# AD9954.net
KiCad netlist of a schematic drawn in Altium Designer
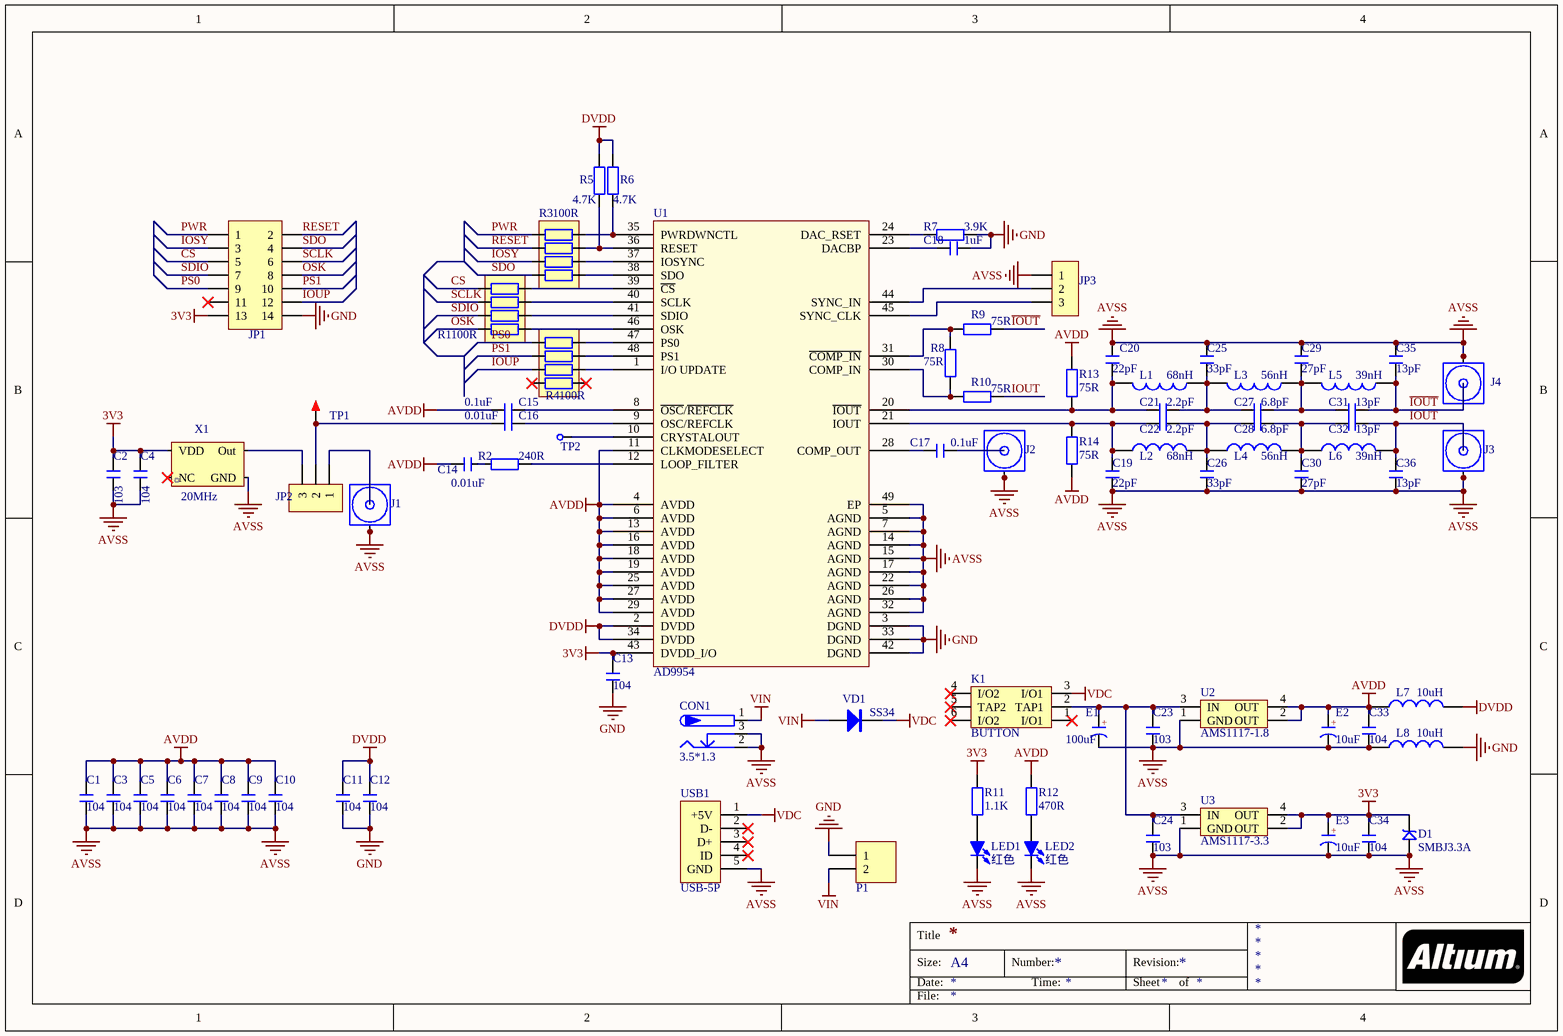
[diagram p0: AD9954模块.SchDoc]

(export (version "E")
  (design (tool "Eeschema 10.0.6"))
  (components
    (comp (ref "C1")
      (value "104")
      (footprint "C 0603")
      (description "无极性贴片电容")
      (fields (field (name "版权归属") "源创客"))
      (libsource (lib "电阻-电容-电感") (part "C"))
    )
    (comp (ref "C2")
      (value "103")
      (footprint "C 0603")
      (description "无极性贴片电容")
      (fields (field (name "版权归属") "源创客"))
      (libsource (lib "电阻-电容-电感") (part "C"))
    )
    (comp (ref "C3")
      (value "104")
      (footprint "C 0603")
      (description "无极性贴片电容")
      (fields (field (name "版权归属") "源创客"))
      (libsource (lib "电阻-电容-电感") (part "C"))
    )
    (comp (ref "C4")
      (value "104")
      (footprint "C 0603")
      (description "无极性贴片电容")
      (fields (field (name "版权归属") "源创客"))
      (libsource (lib "电阻-电容-电感") (part "C"))
    )
    (comp (ref "C5")
      (value "104")
      (footprint "C 0603")
      (description "无极性贴片电容")
      (fields (field (name "版权归属") "源创客"))
      (libsource (lib "电阻-电容-电感") (part "C"))
    )
    (comp (ref "C6")
      (value "104")
      (footprint "C 0603")
      (description "无极性贴片电容")
      (fields (field (name "版权归属") "源创客"))
      (libsource (lib "电阻-电容-电感") (part "C"))
    )
    (comp (ref "C7")
      (value "104")
      (footprint "C 0603")
      (description "无极性贴片电容")
      (fields (field (name "版权归属") "源创客"))
      (libsource (lib "电阻-电容-电感") (part "C"))
    )
    (comp (ref "C8")
      (value "104")
      (footprint "C 0603")
      (description "无极性贴片电容")
      (fields (field (name "版权归属") "源创客"))
      (libsource (lib "电阻-电容-电感") (part "C"))
    )
    (comp (ref "C9")
      (value "104")
      (footprint "C 0603")
      (description "无极性贴片电容")
      (fields (field (name "版权归属") "源创客"))
      (libsource (lib "电阻-电容-电感") (part "C"))
    )
    (comp (ref "C10")
      (value "104")
      (footprint "C 0603")
      (description "无极性贴片电容")
      (fields (field (name "版权归属") "源创客"))
      (libsource (lib "电阻-电容-电感") (part "C"))
    )
    (comp (ref "C11")
      (value "104")
      (footprint "C 0603")
      (description "无极性贴片电容")
      (fields (field (name "版权归属") "源创客"))
      (libsource (lib "电阻-电容-电感") (part "C"))
    )
    (comp (ref "C12")
      (value "104")
      (footprint "C 0603")
      (description "无极性贴片电容")
      (fields (field (name "版权归属") "源创客"))
      (libsource (lib "电阻-电容-电感") (part "C"))
    )
    (comp (ref "C13")
      (value "104")
      (footprint "C 0603")
      (description "无极性贴片电容")
      (fields (field (name "版权归属") "源创客"))
      (libsource (lib "电阻-电容-电感") (part "C"))
    )
    (comp (ref "C14")
      (value "0.01uF")
      (footprint "C 0603")
      (description "无极性贴片电容")
      (fields (field (name "版权归属") "源创客"))
      (libsource (lib "电阻-电容-电感") (part "C"))
    )
    (comp (ref "C15")
      (value "0.1uF")
      (footprint "C 0603")
      (description "无极性贴片电容")
      (fields (field (name "版权归属") "源创客"))
      (libsource (lib "电阻-电容-电感") (part "C"))
    )
    (comp (ref "C16")
      (value "0.01uF")
      (footprint "C 0603")
      (description "无极性贴片电容")
      (fields (field (name "版权归属") "源创客"))
      (libsource (lib "电阻-电容-电感") (part "C"))
    )
    (comp (ref "C17")
      (value "0.1uF")
      (footprint "C 0603")
      (description "无极性贴片电容")
      (fields (field (name "版权归属") "源创客"))
      (libsource (lib "电阻-电容-电感") (part "C"))
    )
    (comp (ref "C18")
      (value "1uF")
      (footprint "C 0603")
      (description "无极性贴片电容")
      (fields (field (name "版权归属") "源创客"))
      (libsource (lib "电阻-电容-电感") (part "C"))
    )
    (comp (ref "C19")
      (value "22pF")
      (footprint "C 0603")
      (description "无极性贴片电容")
      (fields (field (name "版权归属") "源创客"))
      (libsource (lib "电阻-电容-电感") (part "C"))
    )
    (comp (ref "C20")
      (value "22pF")
      (footprint "C 0603")
      (description "无极性贴片电容")
      (fields (field (name "版权归属") "源创客"))
      (libsource (lib "电阻-电容-电感") (part "C"))
    )
    (comp (ref "C21")
      (value "2.2pF")
      (footprint "C 0603")
      (description "无极性贴片电容")
      (fields (field (name "版权归属") "源创客"))
      (libsource (lib "电阻-电容-电感") (part "C"))
    )
    (comp (ref "C22")
      (value "2.2pF")
      (footprint "C 0603")
      (description "无极性贴片电容")
      (fields (field (name "版权归属") "源创客"))
      (libsource (lib "电阻-电容-电感") (part "C"))
    )
    (comp (ref "C23")
      (value "103")
      (footprint "C 0603")
      (description "无极性贴片电容")
      (fields (field (name "版权归属") "源创客"))
      (libsource (lib "电阻-电容-电感") (part "C"))
    )
    (comp (ref "C24")
      (value "103")
      (footprint "C 0603")
      (description "无极性贴片电容")
      (fields (field (name "版权归属") "源创客"))
      (libsource (lib "电阻-电容-电感") (part "C"))
    )
    (comp (ref "C25")
      (value "33pF")
      (footprint "C 0603")
      (description "无极性贴片电容")
      (fields (field (name "版权归属") "源创客"))
      (libsource (lib "电阻-电容-电感") (part "C"))
    )
    (comp (ref "C26")
      (value "33pF")
      (footprint "C 0603")
      (description "无极性贴片电容")
      (fields (field (name "版权归属") "源创客"))
      (libsource (lib "电阻-电容-电感") (part "C"))
    )
    (comp (ref "C27")
      (value "6.8pF")
      (footprint "C 0603")
      (description "无极性贴片电容")
      (fields (field (name "版权归属") "源创客"))
      (libsource (lib "电阻-电容-电感") (part "C"))
    )
    (comp (ref "C28")
      (value "6.8pF")
      (footprint "C 0603")
      (description "无极性贴片电容")
      (fields (field (name "版权归属") "源创客"))
      (libsource (lib "电阻-电容-电感") (part "C"))
    )
    (comp (ref "C29")
      (value "27pF")
      (footprint "C 0603")
      (description "无极性贴片电容")
      (fields (field (name "版权归属") "源创客"))
      (libsource (lib "电阻-电容-电感") (part "C"))
    )
    (comp (ref "C30")
      (value "27pF")
      (footprint "C 0603")
      (description "无极性贴片电容")
      (fields (field (name "版权归属") "源创客"))
      (libsource (lib "电阻-电容-电感") (part "C"))
    )
    (comp (ref "C31")
      (value "13pF")
      (footprint "C 0603")
      (description "无极性贴片电容")
      (fields (field (name "版权归属") "源创客"))
      (libsource (lib "电阻-电容-电感") (part "C"))
    )
    (comp (ref "C32")
      (value "13pF")
      (footprint "C 0603")
      (description "无极性贴片电容")
      (fields (field (name "版权归属") "源创客"))
      (libsource (lib "电阻-电容-电感") (part "C"))
    )
    (comp (ref "C33")
      (value "104")
      (footprint "C 0603")
      (description "无极性贴片电容")
      (fields (field (name "版权归属") "源创客"))
      (libsource (lib "电阻-电容-电感") (part "C"))
    )
    (comp (ref "C34")
      (value "104")
      (footprint "C 0603")
      (description "无极性贴片电容")
      (fields (field (name "版权归属") "源创客"))
      (libsource (lib "电阻-电容-电感") (part "C"))
    )
    (comp (ref "C35")
      (value "13pF")
      (footprint "C 0603")
      (description "无极性贴片电容")
      (fields (field (name "版权归属") "源创客"))
      (libsource (lib "电阻-电容-电感") (part "C"))
    )
    (comp (ref "C36")
      (value "13pF")
      (footprint "C 0603")
      (description "无极性贴片电容")
      (fields (field (name "版权归属") "源创客"))
      (libsource (lib "电阻-电容-电感") (part "C"))
    )
    (comp (ref "CON1")
      (value "3.5*1.3")
      (footprint "DC-005")
      (description "低压电源接口")
      (fields (field (name "版权归属") "源创客"))
      (libsource (lib "接口类") (part "P-DC"))
    )
    (comp (ref "D1")
      (value "SMBJ3.3A")
      (footprint "SMB")
      (description "TVS")
      (libsource (lib "阿波罗STM32F4&F7底板封装库") (part "SMBJ"))
    )
    (comp (ref "E1")
      (value "100uF")
      (footprint "CD B(3528)")
      (description "贴片钽电容")
      (fields (field (name "版权归属") "源创客"))
      (libsource (lib "电阻-电容-电感") (part "C-CD"))
    )
    (comp (ref "E2")
      (value "10uF")
      (footprint "CD B(3528)")
      (description "贴片钽电容")
      (fields (field (name "版权归属") "源创客"))
      (libsource (lib "电阻-电容-电感") (part "C-CD"))
    )
    (comp (ref "E3")
      (value "10uF")
      (footprint "CD B(3528)")
      (description "贴片钽电容")
      (fields (field (name "版权归属") "源创客"))
      (libsource (lib "电阻-电容-电感") (part "C-CD"))
    )
    (comp (ref "J1") (value "COAX") (footprint "MCX5.08-5") (libsource (lib "LIB") (part "COAX")))
    (comp (ref "J2") (value "COAX") (footprint "MCX5.08-5-H") (libsource (lib "LIB") (part "COAX")))
    (comp (ref "J3") (value "COAX") (footprint "MCX5.08-5-H") (libsource (lib "LIB") (part "COAX")))
    (comp (ref "J4") (value "COAX") (footprint "MCX5.08-5-H") (libsource (lib "LIB") (part "COAX")))
    (comp (ref "JP1")
      (value "Header 2X7")
      (footprint "HDR-7X2")
      (description "7*2P接插件")
      (fields (field (name "版权归属") "源创客"))
      (libsource (lib "接插件") (part "Header 7X2"))
    )
    (comp (ref "JP2")
      (value "HDR-1X3")
      (footprint "HDR-1X3")
      (description "3P接插件")
      (fields (field (name "版权归属") "源创客"))
      (libsource (lib "接插件") (part "Header 3"))
    )
    (comp (ref "JP3")
      (value "HDR-1X3")
      (footprint "HDR-1X3")
      (description "3P接插件")
      (fields (field (name "版权归属") "源创客"))
      (libsource (lib "") (part "Header 3_1"))
    )
    (comp (ref "K1")
      (value "BUTTON")
      (footprint "KFT DIP-8X8")
      (libsource (lib "阿波罗STM32F4&F7底板封装库") (part "BUTTON"))
    )
    (comp (ref "L1")
      (value "68nH")
      (footprint "L 0603")
      (description "小功率贴片电感")
      (fields (field (name "版权归属") "源创客"))
      (libsource (lib "电阻-电容-电感") (part "L"))
    )
    (comp (ref "L2")
      (value "68nH")
      (footprint "L 0603")
      (description "小功率贴片电感")
      (fields (field (name "版权归属") "源创客"))
      (libsource (lib "电阻-电容-电感") (part "L"))
    )
    (comp (ref "L3")
      (value "56nH")
      (footprint "L 0603")
      (description "小功率贴片电感")
      (fields (field (name "版权归属") "源创客"))
      (libsource (lib "电阻-电容-电感") (part "L"))
    )
    (comp (ref "L4")
      (value "56nH")
      (footprint "L 0603")
      (description "小功率贴片电感")
      (fields (field (name "版权归属") "源创客"))
      (libsource (lib "电阻-电容-电感") (part "L"))
    )
    (comp (ref "L5")
      (value "39nH")
      (footprint "L 0603")
      (description "小功率贴片电感")
      (fields (field (name "版权归属") "源创客"))
      (libsource (lib "电阻-电容-电感") (part "L"))
    )
    (comp (ref "L6")
      (value "39nH")
      (footprint "L 0603")
      (description "小功率贴片电感")
      (fields (field (name "版权归属") "源创客"))
      (libsource (lib "电阻-电容-电感") (part "L"))
    )
    (comp (ref "L7")
      (value "10uH")
      (footprint "L 0805")
      (description "小功率贴片电感")
      (fields (field (name "版权归属") "源创客"))
      (libsource (lib "电阻-电容-电感") (part "L"))
    )
    (comp (ref "L8")
      (value "10uH")
      (footprint "L 0805")
      (description "小功率贴片电感")
      (fields (field (name "版权归属") "源创客"))
      (libsource (lib "电阻-电容-电感") (part "L"))
    )
    (comp (ref "LED1")
      (value "红色")
      (footprint "LED 0805G")
      (description "贴片LED")
      (fields (field (name "版权归属") "源创客"))
      (libsource (lib "LED") (part "LED-SMD"))
    )
    (comp (ref "LED2")
      (value "红色")
      (footprint "LED 0805G")
      (description "贴片LED")
      (fields (field (name "版权归属") "源创客"))
      (libsource (lib "LED") (part "LED-SMD"))
    )
    (comp (ref "P1")
      (value "Header 2")
      (footprint "HDR2X1_B2")
      (description "接插件")
      (fields (field (name "PUBLISHER") "Altium Limited"))
      (libsource (lib "LIB") (part "Header 2"))
    )
    (comp (ref "R1")
      (value "100R")
      (footprint "RCA-8P4R-0603")
      (description "贴片网络排阻")
      (fields (field (name "版权归属") "源创客"))
      (libsource (lib "电阻-电容-电感") (part "R-8P4R"))
    )
    (comp (ref "R2")
      (value "240R")
      (footprint "R 0603")
      (description "贴片电阻")
      (fields (field (name "版权归属") "源创客"))
      (libsource (lib "电阻-电容-电感") (part "R"))
    )
    (comp (ref "R3")
      (value "100R")
      (footprint "RCA-8P4R-0603")
      (description "贴片网络排阻")
      (fields (field (name "版权归属") "源创客"))
      (libsource (lib "电阻-电容-电感") (part "R-8P4R"))
    )
    (comp (ref "R4")
      (value "100R")
      (footprint "RCA-8P4R-0603")
      (description "贴片网络排阻")
      (fields (field (name "版权归属") "源创客"))
      (libsource (lib "电阻-电容-电感") (part "R-8P4R"))
    )
    (comp (ref "R5")
      (value "4.7K")
      (footprint "R 0603")
      (description "贴片电阻")
      (fields (field (name "版权归属") "源创客"))
      (libsource (lib "电阻-电容-电感") (part "R"))
    )
    (comp (ref "R6")
      (value "4.7K")
      (footprint "R 0603")
      (description "贴片电阻")
      (fields (field (name "版权归属") "源创客"))
      (libsource (lib "电阻-电容-电感") (part "R"))
    )
    (comp (ref "R7")
      (value "3.9K")
      (footprint "R 0603")
      (description "贴片电阻")
      (fields (field (name "版权归属") "源创客"))
      (libsource (lib "电阻-电容-电感") (part "R"))
    )
    (comp (ref "R8")
      (value "75R")
      (footprint "R 0603")
      (description "贴片电阻")
      (fields (field (name "版权归属") "源创客"))
      (libsource (lib "电阻-电容-电感") (part "R"))
    )
    (comp (ref "R9")
      (value "75R")
      (footprint "R 0603")
      (description "贴片电阻")
      (fields (field (name "版权归属") "源创客"))
      (libsource (lib "电阻-电容-电感") (part "R"))
    )
    (comp (ref "R10")
      (value "75R")
      (footprint "R 0603")
      (description "贴片电阻")
      (fields (field (name "版权归属") "源创客"))
      (libsource (lib "电阻-电容-电感") (part "R"))
    )
    (comp (ref "R11")
      (value "1.1K")
      (footprint "R 0603")
      (description "贴片电阻")
      (fields (field (name "版权归属") "源创客"))
      (libsource (lib "电阻-电容-电感") (part "R"))
    )
    (comp (ref "R12")
      (value "470R")
      (footprint "R 0603")
      (description "贴片电阻")
      (fields (field (name "版权归属") "源创客"))
      (libsource (lib "电阻-电容-电感") (part "R"))
    )
    (comp (ref "R13")
      (value "75R")
      (footprint "R 0603")
      (description "贴片电阻")
      (fields (field (name "版权归属") "源创客"))
      (libsource (lib "电阻-电容-电感") (part "R"))
    )
    (comp (ref "R14")
      (value "75R")
      (footprint "R 0603")
      (description "贴片电阻")
      (fields (field (name "版权归属") "源创客"))
      (libsource (lib "电阻-电容-电感") (part "R"))
    )
    (comp (ref "TP1")
      (value "TEST TP")
      (footprint "TEST TP1.4_B")
      (description "测试环")
      (fields (field (name "版权归属") "源创客"))
      (libsource (lib "未分类器件") (part "TEST TP"))
    )
    (comp (ref "TP2")
      (value "CHECK")
      (footprint "CHECK-C")
      (description "测试点")
      (libsource (lib "LIB") (part "CHECK"))
    )
    (comp (ref "U1")
      (value "AD9954")
      (footprint "SV_48_4")
      (description "400MSPS、14位、1.8V CMOS、直接数字频率合成器")
      (fields (field (name "MANUFACTURER_PART_NUMBER") "AD9954YSVZ"))
      (libsource (lib "MyLibray") (part "AD9954YSVZ"))
    )
    (comp (ref "U2")
      (value "AMS1117-1.8")
      (footprint "SOT223_N")
      (libsource (lib "ATK-7016&7084 7寸RGB屏模块封装库") (part "AMS1117"))
    )
    (comp (ref "U3")
      (value "AMS1117-3.3")
      (footprint "SOT223_N")
      (libsource (lib "ATK-7016&7084 7寸RGB屏模块封装库") (part "AMS1117"))
    )
    (comp (ref "USB1")
      (value "USB-5P")
      (footprint "USB-MICRO_B")
      (description "微型USB母座")
      (fields (field (name "版权归属") "源创客"))
      (libsource (lib "接口类") (part "USB-5P"))
    )
    (comp (ref "VD1")
      (value "SS34")
      (footprint "DIODE-SMA")
      (description "肖特基二极管")
      (fields (field (name "版权归属") "源创客"))
      (libsource (lib "二极管-整流桥") (part "SS34"))
    )
    (comp (ref "X1")
      (value "XTAL")
      (footprint "X-CPX75")
      (description "有源晶振")
      (fields (field (name "FREQUENCY") "20MHz"))
      (libsource (lib "LIB") (part "XTAL_Oscillator"))
    )
  )
  (nets
    (net (code "1") (name "/CS") (class "Default")
      (node (ref "JP1") (pin "5") (pinfunction "5_5") (pintype "passive"))
      (node (ref "R1") (pin "1") (pinfunction "1_1") (pintype "passive"))
    )
    (net (code "2") (name "/IOSY") (class "Default")
      (node (ref "JP1") (pin "3") (pinfunction "3_3") (pintype "passive"))
      (node (ref "R3") (pin "3") (pinfunction "3_3") (pintype "passive"))
    )
    (net (code "3") (name "/IOUP") (class "Default")
      (node (ref "JP1") (pin "12") (pinfunction "12_12") (pintype "passive"))
      (node (ref "R4") (pin "3") (pinfunction "3_3") (pintype "passive"))
    )
    (net (code "4") (name "/IOUT") (class "Default")
      (node (ref "C32") (pin "1") (pinfunction "1_1") (pintype "passive"))
      (node (ref "C36") (pin "1") (pinfunction "1_1") (pintype "passive"))
      (node (ref "J3") (pin "1") (pinfunction "Signal_1") (pintype "passive"))
      (node (ref "L6") (pin "2") (pinfunction "2_2") (pintype "passive"))
      (node (ref "R10") (pin "1") (pinfunction "1_1") (pintype "passive"))
    )
    (net (code "5") (name "/OSK") (class "Default")
      (node (ref "JP1") (pin "8") (pinfunction "8_8") (pintype "passive"))
      (node (ref "R1") (pin "4") (pinfunction "4_4") (pintype "passive"))
    )
    (net (code "6") (name "/PS0") (class "Default")
      (node (ref "JP1") (pin "9") (pinfunction "9_9") (pintype "passive"))
      (node (ref "R4") (pin "1") (pinfunction "1_1") (pintype "passive"))
    )
    (net (code "7") (name "/PS1") (class "Default")
      (node (ref "JP1") (pin "10") (pinfunction "10_10") (pintype "passive"))
      (node (ref "R4") (pin "2") (pinfunction "2_2") (pintype "passive"))
    )
    (net (code "8") (name "/PWR") (class "Default")
      (node (ref "JP1") (pin "1") (pinfunction "1_1") (pintype "passive"))
      (node (ref "R3") (pin "1") (pinfunction "1_1") (pintype "passive"))
    )
    (net (code "9") (name "/RESET") (class "Default")
      (node (ref "JP1") (pin "2") (pinfunction "2_2") (pintype "passive"))
      (node (ref "R3") (pin "2") (pinfunction "2_2") (pintype "passive"))
    )
    (net (code "10") (name "/SCLK") (class "Default")
      (node (ref "JP1") (pin "6") (pinfunction "6_6") (pintype "passive"))
      (node (ref "R1") (pin "2") (pinfunction "2_2") (pintype "passive"))
    )
    (net (code "11") (name "/SDIO") (class "Default")
      (node (ref "JP1") (pin "7") (pinfunction "7_7") (pintype "passive"))
      (node (ref "R1") (pin "3") (pinfunction "3_3") (pintype "passive"))
    )
    (net (code "12") (name "/SDO") (class "Default")
      (node (ref "JP1") (pin "4") (pinfunction "4_4") (pintype "passive"))
      (node (ref "R3") (pin "4") (pinfunction "4_4") (pintype "passive"))
    )
    (net (code "13") (name "/~{IOUT}") (class "Default")
      (node (ref "C31") (pin "2") (pinfunction "2_2") (pintype "passive"))
      (node (ref "C35") (pin "1") (pinfunction "1_1") (pintype "passive"))
      (node (ref "J4") (pin "1") (pinfunction "Signal_1") (pintype "passive"))
      (node (ref "L5") (pin "1") (pinfunction "1_1") (pintype "passive"))
      (node (ref "R9") (pin "1") (pinfunction "1_1") (pintype "passive"))
    )
    (net (code "14") (name "3V3") (class "Default")
      (node (ref "C13") (pin "2") (pinfunction "2_2") (pintype "passive"))
      (node (ref "C2") (pin "2") (pinfunction "2_2") (pintype "passive"))
      (node (ref "C34") (pin "2") (pinfunction "2_2") (pintype "passive"))
      (node (ref "C4") (pin "2") (pinfunction "2_2") (pintype "passive"))
      (node (ref "D1") (pin "2") (pintype "passive"))
      (node (ref "E3") (pin "1") (pinfunction "A_1") (pintype "passive"))
      (node (ref "JP1") (pin "13") (pinfunction "13_13") (pintype "passive"))
      (node (ref "R11") (pin "2") (pinfunction "2_2") (pintype "passive"))
      (node (ref "U1") (pin "43") (pinfunction "DVDD_I/O_43") (pintype "power_in"))
      (node (ref "U3") (pin "2") (pinfunction "OUT_2") (pintype "passive"))
      (node (ref "U3") (pin "4") (pinfunction "OUT_4") (pintype "passive"))
      (node (ref "X1") (pin "4") (pinfunction "VDD_4") (pintype "passive"))
    )
    (net (code "15") (name "AVDD") (class "Default")
      (node (ref "C1") (pin "2") (pinfunction "2_2") (pintype "passive"))
      (node (ref "C10") (pin "2") (pinfunction "2_2") (pintype "passive"))
      (node (ref "C14") (pin "1") (pinfunction "1_1") (pintype "passive"))
      (node (ref "C15") (pin "1") (pinfunction "1_1") (pintype "passive"))
      (node (ref "C3") (pin "2") (pinfunction "2_2") (pintype "passive"))
      (node (ref "C33") (pin "2") (pinfunction "2_2") (pintype "passive"))
      (node (ref "C5") (pin "2") (pinfunction "2_2") (pintype "passive"))
      (node (ref "C6") (pin "2") (pinfunction "2_2") (pintype "passive"))
      (node (ref "C7") (pin "2") (pinfunction "2_2") (pintype "passive"))
      (node (ref "C8") (pin "2") (pinfunction "2_2") (pintype "passive"))
      (node (ref "C9") (pin "2") (pinfunction "2_2") (pintype "passive"))
      (node (ref "E2") (pin "1") (pinfunction "A_1") (pintype "passive"))
      (node (ref "L7") (pin "1") (pinfunction "1_1") (pintype "passive"))
      (node (ref "R12") (pin "2") (pinfunction "2_2") (pintype "passive"))
      (node (ref "R13") (pin "2") (pinfunction "2_2") (pintype "passive"))
      (node (ref "R14") (pin "1") (pinfunction "1_1") (pintype "passive"))
      (node (ref "U1") (pin "11") (pinfunction "CLKMODESELECT_11") (pintype "passive"))
      (node (ref "U1") (pin "13") (pinfunction "AVDD_13") (pintype "power_in"))
      (node (ref "U1") (pin "16") (pinfunction "AVDD_16") (pintype "power_in"))
      (node (ref "U1") (pin "18") (pinfunction "AVDD_18") (pintype "power_in"))
      (node (ref "U1") (pin "19") (pinfunction "AVDD_19") (pintype "power_in"))
      (node (ref "U1") (pin "25") (pinfunction "AVDD_25") (pintype "power_in"))
      (node (ref "U1") (pin "27") (pinfunction "AVDD_27") (pintype "power_in"))
      (node (ref "U1") (pin "29") (pinfunction "AVDD_29") (pintype "power_in"))
      (node (ref "U1") (pin "4") (pinfunction "AVDD_4") (pintype "power_in"))
      (node (ref "U1") (pin "6") (pinfunction "AVDD_6") (pintype "power_in"))
      (node (ref "U2") (pin "2") (pinfunction "OUT_2") (pintype "passive"))
      (node (ref "U2") (pin "4") (pinfunction "OUT_4") (pintype "passive"))
    )
    (net (code "16") (name "AVSS") (class "Default")
      (node (ref "C1") (pin "1") (pinfunction "1_1") (pintype "passive"))
      (node (ref "C10") (pin "1") (pinfunction "1_1") (pintype "passive"))
      (node (ref "C19") (pin "2") (pinfunction "2_2") (pintype "passive"))
      (node (ref "C2") (pin "1") (pinfunction "1_1") (pintype "passive"))
      (node (ref "C20") (pin "2") (pinfunction "2_2") (pintype "passive"))
      (node (ref "C23") (pin "1") (pinfunction "1_1") (pintype "passive"))
      (node (ref "C24") (pin "1") (pinfunction "1_1") (pintype "passive"))
      (node (ref "C25") (pin "2") (pinfunction "2_2") (pintype "passive"))
      (node (ref "C26") (pin "2") (pinfunction "2_2") (pintype "passive"))
      (node (ref "C29") (pin "2") (pinfunction "2_2") (pintype "passive"))
      (node (ref "C3") (pin "1") (pinfunction "1_1") (pintype "passive"))
      (node (ref "C30") (pin "2") (pinfunction "2_2") (pintype "passive"))
      (node (ref "C33") (pin "1") (pinfunction "1_1") (pintype "passive"))
      (node (ref "C34") (pin "1") (pinfunction "1_1") (pintype "passive"))
      (node (ref "C35") (pin "2") (pinfunction "2_2") (pintype "passive"))
      (node (ref "C36") (pin "2") (pinfunction "2_2") (pintype "passive"))
      (node (ref "C4") (pin "1") (pinfunction "1_1") (pintype "passive"))
      (node (ref "C5") (pin "1") (pinfunction "1_1") (pintype "passive"))
      (node (ref "C6") (pin "1") (pinfunction "1_1") (pintype "passive"))
      (node (ref "C7") (pin "1") (pinfunction "1_1") (pintype "passive"))
      (node (ref "C8") (pin "1") (pinfunction "1_1") (pintype "passive"))
      (node (ref "C9") (pin "1") (pinfunction "1_1") (pintype "passive"))
      (node (ref "CON1") (pin "2") (pintype "power_in"))
      (node (ref "CON1") (pin "3") (pintype "power_in"))
      (node (ref "D1") (pin "1") (pintype "passive"))
      (node (ref "E1") (pin "2") (pinfunction "K_2") (pintype "passive"))
      (node (ref "E2") (pin "2") (pinfunction "K_2") (pintype "passive"))
      (node (ref "E3") (pin "2") (pinfunction "K_2") (pintype "passive"))
      (node (ref "J1") (pin "2") (pinfunction "GND_2") (pintype "passive"))
      (node (ref "J1") (pin "3") (pinfunction "GND_3") (pintype "passive"))
      (node (ref "J1") (pin "4") (pinfunction "GND_4") (pintype "passive"))
      (node (ref "J1") (pin "5") (pinfunction "GND_5") (pintype "passive"))
      (node (ref "J2") (pin "2") (pinfunction "GND_2") (pintype "passive"))
      (node (ref "J2") (pin "3") (pinfunction "GND_3") (pintype "passive"))
      (node (ref "J2") (pin "4") (pinfunction "GND_4") (pintype "passive"))
      (node (ref "J2") (pin "5") (pinfunction "GND_5") (pintype "passive"))
      (node (ref "J3") (pin "2") (pinfunction "GND_2") (pintype "passive"))
      (node (ref "J3") (pin "3") (pinfunction "GND_3") (pintype "passive"))
      (node (ref "J3") (pin "4") (pinfunction "GND_4") (pintype "passive"))
      (node (ref "J3") (pin "5") (pinfunction "GND_5") (pintype "passive"))
      (node (ref "J4") (pin "2") (pinfunction "GND_2") (pintype "passive"))
      (node (ref "J4") (pin "3") (pinfunction "GND_3") (pintype "passive"))
      (node (ref "J4") (pin "4") (pinfunction "GND_4") (pintype "passive"))
      (node (ref "J4") (pin "5") (pinfunction "GND_5") (pintype "passive"))
      (node (ref "JP3") (pin "1") (pinfunction "1_1") (pintype "passive"))
      (node (ref "L8") (pin "1") (pinfunction "1_1") (pintype "passive"))
      (node (ref "LED1") (pin "2") (pinfunction "K_2") (pintype "passive"))
      (node (ref "LED2") (pin "2") (pinfunction "K_2") (pintype "passive"))
      (node (ref "U1") (pin "14") (pinfunction "AGND_14") (pintype "passive"))
      (node (ref "U1") (pin "15") (pinfunction "AGND_15") (pintype "passive"))
      (node (ref "U1") (pin "17") (pinfunction "AGND_17") (pintype "passive"))
      (node (ref "U1") (pin "22") (pinfunction "AGND_22") (pintype "passive"))
      (node (ref "U1") (pin "26") (pinfunction "AGND_26") (pintype "passive"))
      (node (ref "U1") (pin "32") (pinfunction "AGND_32") (pintype "passive"))
      (node (ref "U1") (pin "49") (pinfunction "EP_49") (pintype "passive"))
      (node (ref "U1") (pin "5") (pinfunction "AGND_5") (pintype "passive"))
      (node (ref "U1") (pin "7") (pinfunction "AGND_7") (pintype "passive"))
      (node (ref "U2") (pin "1") (pinfunction "GND_1") (pintype "passive"))
      (node (ref "U3") (pin "1") (pinfunction "GND_1") (pintype "passive"))
      (node (ref "USB1") (pin "5") (pinfunction "GND_5") (pintype "passive"))
      (node (ref "X1") (pin "2") (pinfunction "GND_2") (pintype "passive"))
    )
    (net (code "17") (name "DVDD") (class "Default")
      (node (ref "C11") (pin "2") (pinfunction "2_2") (pintype "passive"))
      (node (ref "C12") (pin "2") (pinfunction "2_2") (pintype "passive"))
      (node (ref "L7") (pin "2") (pinfunction "2_2") (pintype "passive"))
      (node (ref "R5") (pin "2") (pinfunction "2_2") (pintype "passive"))
      (node (ref "R6") (pin "2") (pinfunction "2_2") (pintype "passive"))
      (node (ref "U1") (pin "2") (pinfunction "DVDD_2") (pintype "power_in"))
      (node (ref "U1") (pin "34") (pinfunction "DVDD_34") (pintype "power_in"))
    )
    (net (code "18") (name "GND") (class "Default")
      (node (ref "C11") (pin "1") (pinfunction "1_1") (pintype "passive"))
      (node (ref "C12") (pin "1") (pinfunction "1_1") (pintype "passive"))
      (node (ref "C13") (pin "1") (pinfunction "1_1") (pintype "passive"))
      (node (ref "C18") (pin "2") (pinfunction "2_2") (pintype "passive"))
      (node (ref "JP1") (pin "14") (pinfunction "14_14") (pintype "passive"))
      (node (ref "L8") (pin "2") (pinfunction "2_2") (pintype "passive"))
      (node (ref "P1") (pin "1") (pinfunction "1_1") (pintype "passive"))
      (node (ref "R7") (pin "2") (pinfunction "2_2") (pintype "passive"))
      (node (ref "U1") (pin "3") (pinfunction "DGND_3") (pintype "passive"))
      (node (ref "U1") (pin "33") (pinfunction "DGND_33") (pintype "passive"))
      (node (ref "U1") (pin "42") (pinfunction "DGND_42") (pintype "passive"))
    )
    (net (code "19") (name "Net-(C14-Pad2)") (class "Default")
      (node (ref "C14") (pin "2") (pinfunction "2_2") (pintype "passive"))
      (node (ref "R2") (pin "1") (pinfunction "1_1") (pintype "passive"))
    )
    (net (code "20") (name "Net-(C16-Pad1)") (class "Default")
      (node (ref "C16") (pin "1") (pinfunction "1_1") (pintype "passive"))
      (node (ref "JP2") (pin "2") (pinfunction "2_2") (pintype "passive"))
      (node (ref "TP1") (pin "1") (pinfunction "1_1") (pintype "passive"))
    )
    (net (code "21") (name "Net-(C21-Pad2)") (class "Default")
      (node (ref "C21") (pin "2") (pinfunction "2_2") (pintype "passive"))
      (node (ref "C25") (pin "1") (pinfunction "1_1") (pintype "passive"))
      (node (ref "C27") (pin "1") (pinfunction "1_1") (pintype "passive"))
      (node (ref "L1") (pin "1") (pinfunction "1_1") (pintype "passive"))
      (node (ref "L3") (pin "2") (pinfunction "2_2") (pintype "passive"))
    )
    (net (code "22") (name "Net-(C22-Pad1)") (class "Default")
      (node (ref "C22") (pin "1") (pinfunction "1_1") (pintype "passive"))
      (node (ref "C26") (pin "1") (pinfunction "1_1") (pintype "passive"))
      (node (ref "C28") (pin "2") (pinfunction "2_2") (pintype "passive"))
      (node (ref "L2") (pin "2") (pinfunction "2_2") (pintype "passive"))
      (node (ref "L4") (pin "1") (pinfunction "1_1") (pintype "passive"))
    )
    (net (code "23") (name "Net-(C27-Pad2)") (class "Default")
      (node (ref "C27") (pin "2") (pinfunction "2_2") (pintype "passive"))
      (node (ref "C29") (pin "1") (pinfunction "1_1") (pintype "passive"))
      (node (ref "C31") (pin "1") (pinfunction "1_1") (pintype "passive"))
      (node (ref "L3") (pin "1") (pinfunction "1_1") (pintype "passive"))
      (node (ref "L5") (pin "2") (pinfunction "2_2") (pintype "passive"))
    )
    (net (code "24") (name "Net-(C28-Pad1)") (class "Default")
      (node (ref "C28") (pin "1") (pinfunction "1_1") (pintype "passive"))
      (node (ref "C30") (pin "1") (pinfunction "1_1") (pintype "passive"))
      (node (ref "C32") (pin "2") (pinfunction "2_2") (pintype "passive"))
      (node (ref "L4") (pin "2") (pinfunction "2_2") (pintype "passive"))
      (node (ref "L6") (pin "1") (pinfunction "1_1") (pintype "passive"))
    )
    (net (code "25") (name "Net-(E1-A)") (class "Default")
      (node (ref "C23") (pin "2") (pinfunction "2_2") (pintype "passive"))
      (node (ref "C24") (pin "2") (pinfunction "2_2") (pintype "passive"))
      (node (ref "E1") (pin "1") (pinfunction "A_1") (pintype "passive"))
      (node (ref "K1") (pin "2") (pinfunction "TAP1_2") (pintype "passive"))
      (node (ref "U2") (pin "3") (pinfunction "IN_3") (pintype "passive"))
      (node (ref "U3") (pin "3") (pinfunction "IN_3") (pintype "passive"))
    )
    (net (code "26") (name "Net-(J1-Signal)") (class "Default")
      (node (ref "J1") (pin "1") (pinfunction "Signal_1") (pintype "passive"))
      (node (ref "JP2") (pin "1") (pinfunction "1_1") (pintype "passive"))
    )
    (net (code "27") (name "Net-(J2-Signal)") (class "Default")
      (node (ref "C17") (pin "2") (pinfunction "2_2") (pintype "passive"))
      (node (ref "J2") (pin "1") (pinfunction "Signal_1") (pintype "passive"))
    )
    (net (code "28") (name "Net-(LED1-A)") (class "Default")
      (node (ref "LED1") (pin "1") (pinfunction "A_1") (pintype "passive"))
      (node (ref "R11") (pin "1") (pinfunction "1_1") (pintype "passive"))
    )
    (net (code "29") (name "Net-(LED2-A)") (class "Default")
      (node (ref "LED2") (pin "1") (pinfunction "A_1") (pintype "passive"))
      (node (ref "R12") (pin "1") (pinfunction "1_1") (pintype "passive"))
    )
    (net (code "30") (name "Net-(U1-COMP_IN)") (class "Default")
      (node (ref "R10") (pin "2") (pinfunction "2_2") (pintype "passive"))
      (node (ref "R8") (pin "1") (pinfunction "1_1") (pintype "passive"))
      (node (ref "U1") (pin "30") (pinfunction "COMP_IN_30") (pintype "passive"))
    )
    (net (code "31") (name "Net-(U1-COMP_OUT)") (class "Default")
      (node (ref "C17") (pin "1") (pinfunction "1_1") (pintype "passive"))
      (node (ref "U1") (pin "28") (pinfunction "COMP_OUT_28") (pintype "passive"))
    )
    (net (code "32") (name "Net-(U1-CRYSTALOUT)") (class "Default")
      (node (ref "TP2") (pin "1") (pinfunction "1_1") (pintype "passive"))
      (node (ref "U1") (pin "10") (pinfunction "CRYSTALOUT_10") (pintype "passive"))
    )
    (net (code "33") (name "Net-(U1-DACBP)") (class "Default")
      (node (ref "C18") (pin "1") (pinfunction "1_1") (pintype "passive"))
      (node (ref "U1") (pin "23") (pinfunction "DACBP_23") (pintype "passive"))
    )
    (net (code "34") (name "Net-(U1-DAC_RSET)") (class "Default")
      (node (ref "R7") (pin "1") (pinfunction "1_1") (pintype "passive"))
      (node (ref "U1") (pin "24") (pinfunction "DAC_RSET_24") (pintype "passive"))
    )
    (net (code "35") (name "Net-(U1-IOSYNC)") (class "Default")
      (node (ref "R3") (pin "6") (pinfunction "6_6") (pintype "passive"))
      (node (ref "U1") (pin "37") (pinfunction "IOSYNC_37") (pintype "passive"))
    )
    (net (code "36") (name "Net-(U1-IOUT)") (class "Default")
      (node (ref "C19") (pin "1") (pinfunction "1_1") (pintype "passive"))
      (node (ref "C22") (pin "2") (pinfunction "2_2") (pintype "passive"))
      (node (ref "L2") (pin "1") (pinfunction "1_1") (pintype "passive"))
      (node (ref "R14") (pin "2") (pinfunction "2_2") (pintype "passive"))
      (node (ref "U1") (pin "21") (pinfunction "IOUT_21") (pintype "passive"))
    )
    (net (code "37") (name "Net-(U1-I{slash}O_UPDATE)") (class "Default")
      (node (ref "R4") (pin "6") (pinfunction "6_6") (pintype "passive"))
      (node (ref "U1") (pin "1") (pinfunction "I/O_UPDATE_1") (pintype "passive"))
    )
    (net (code "38") (name "Net-(U1-LOOP_FILTER)") (class "Default")
      (node (ref "R2") (pin "2") (pinfunction "2_2") (pintype "passive"))
      (node (ref "U1") (pin "12") (pinfunction "LOOP_FILTER_12") (pintype "passive"))
    )
    (net (code "39") (name "Net-(U1-OSC{slash}REFCLK)") (class "Default")
      (node (ref "C16") (pin "2") (pinfunction "2_2") (pintype "passive"))
      (node (ref "U1") (pin "9") (pinfunction "OSC/REFCLK_9") (pintype "passive"))
    )
    (net (code "40") (name "Net-(U1-OSK)") (class "Default")
      (node (ref "R1") (pin "5") (pinfunction "5_5") (pintype "passive"))
      (node (ref "U1") (pin "46") (pinfunction "OSK_46") (pintype "passive"))
    )
    (net (code "41") (name "Net-(U1-PS0)") (class "Default")
      (node (ref "R4") (pin "8") (pinfunction "8_8") (pintype "passive"))
      (node (ref "U1") (pin "47") (pinfunction "PS0_47") (pintype "passive"))
    )
    (net (code "42") (name "Net-(U1-PS1)") (class "Default")
      (node (ref "R4") (pin "7") (pinfunction "7_7") (pintype "passive"))
      (node (ref "U1") (pin "48") (pinfunction "PS1_48") (pintype "passive"))
    )
    (net (code "43") (name "Net-(U1-PWRDWNCTL)") (class "Default")
      (node (ref "R3") (pin "8") (pinfunction "8_8") (pintype "passive"))
      (node (ref "R6") (pin "1") (pinfunction "1_1") (pintype "passive"))
      (node (ref "U1") (pin "35") (pinfunction "PWRDWNCTL_35") (pintype "passive"))
    )
    (net (code "44") (name "Net-(U1-RESET)") (class "Default")
      (node (ref "R3") (pin "7") (pinfunction "7_7") (pintype "passive"))
      (node (ref "R5") (pin "1") (pinfunction "1_1") (pintype "passive"))
      (node (ref "U1") (pin "36") (pinfunction "RESET_36") (pintype "passive"))
    )
    (net (code "45") (name "Net-(U1-SCLK)") (class "Default")
      (node (ref "R1") (pin "7") (pinfunction "7_7") (pintype "passive"))
      (node (ref "U1") (pin "40") (pinfunction "SCLK_40") (pintype "passive"))
    )
    (net (code "46") (name "Net-(U1-SDIO)") (class "Default")
      (node (ref "R1") (pin "6") (pinfunction "6_6") (pintype "passive"))
      (node (ref "U1") (pin "41") (pinfunction "SDIO_41") (pintype "passive"))
    )
    (net (code "47") (name "Net-(U1-SDO)") (class "Default")
      (node (ref "R3") (pin "5") (pinfunction "5_5") (pintype "passive"))
      (node (ref "U1") (pin "38") (pinfunction "SDO_38") (pintype "passive"))
    )
    (net (code "48") (name "Net-(U1-SYNC_CLK)") (class "Default")
      (node (ref "JP3") (pin "3") (pinfunction "3_3") (pintype "passive"))
      (node (ref "U1") (pin "45") (pinfunction "SYNC_CLK_45") (pintype "passive"))
    )
    (net (code "49") (name "Net-(U1-SYNC_IN)") (class "Default")
      (node (ref "JP3") (pin "2") (pinfunction "2_2") (pintype "passive"))
      (node (ref "U1") (pin "44") (pinfunction "SYNC_IN_44") (pintype "passive"))
    )
    (net (code "50") (name "Net-(U1-~{COMP_IN})") (class "Default")
      (node (ref "R8") (pin "2") (pinfunction "2_2") (pintype "passive"))
      (node (ref "R9") (pin "2") (pinfunction "2_2") (pintype "passive"))
      (node (ref "U1") (pin "31") (pinfunction "~{COMP_IN}_31") (pintype "passive"))
    )
    (net (code "51") (name "Net-(U1-~{CS})") (class "Default")
      (node (ref "R1") (pin "8") (pinfunction "8_8") (pintype "passive"))
      (node (ref "U1") (pin "39") (pinfunction "~{CS}_39") (pintype "passive"))
    )
    (net (code "52") (name "Net-(U1-~{IOUT})") (class "Default")
      (node (ref "C20") (pin "1") (pinfunction "1_1") (pintype "passive"))
      (node (ref "C21") (pin "1") (pinfunction "1_1") (pintype "passive"))
      (node (ref "L1") (pin "2") (pinfunction "2_2") (pintype "passive"))
      (node (ref "R13") (pin "1") (pinfunction "1_1") (pintype "passive"))
      (node (ref "U1") (pin "20") (pinfunction "~{IOUT}_20") (pintype "passive"))
    )
    (net (code "53") (name "Net-(U1-~{OSC}{slash}~{REFCLK})") (class "Default")
      (node (ref "C15") (pin "2") (pinfunction "2_2") (pintype "passive"))
      (node (ref "U1") (pin "8") (pinfunction "~{OSC}/~{REFCLK}_8") (pintype "passive"))
    )
    (net (code "54") (name "Net-(X1-Out)") (class "Default")
      (node (ref "JP2") (pin "3") (pinfunction "3_3") (pintype "passive"))
      (node (ref "X1") (pin "3") (pinfunction "Out_3") (pintype "passive"))
    )
    (net (code "55") (name "VDC") (class "Default")
      (node (ref "K1") (pin "3") (pinfunction "I/O1_3") (pintype "passive"))
      (node (ref "USB1") (pin "1") (pinfunction "+5V_1") (pintype "passive"))
      (node (ref "VD1") (pin "2") (pinfunction "K_2") (pintype "passive"))
    )
    (net (code "56") (name "VIN") (class "Default")
      (node (ref "CON1") (pin "1") (pintype "power_in"))
      (node (ref "P1") (pin "2") (pinfunction "2_2") (pintype "passive"))
      (node (ref "VD1") (pin "1") (pinfunction "A_1") (pintype "passive"))
    )
    (net (code "57") (name "unconnected-(JP1-Pad11)") (class "Default")
      (node (ref "JP1") (pin "11") (pinfunction "11_11") (pintype "passive+no_connect"))
    )
    (net (code "58") (name "unconnected-(K1-I{slash}O1-Pad1)") (class "Default")
      (node (ref "K1") (pin "1") (pinfunction "I/O1_1") (pintype "passive+no_connect"))
    )
    (net (code "59") (name "unconnected-(K1-I{slash}O2-Pad4)") (class "Default")
      (node (ref "K1") (pin "4") (pinfunction "I/O2_4") (pintype "passive+no_connect"))
    )
    (net (code "60") (name "unconnected-(K1-I{slash}O2-Pad6)") (class "Default")
      (node (ref "K1") (pin "6") (pinfunction "I/O2_6") (pintype "passive+no_connect"))
    )
    (net (code "61") (name "unconnected-(K1-TAP2-Pad5)") (class "Default")
      (node (ref "K1") (pin "5") (pinfunction "TAP2_5") (pintype "passive+no_connect"))
    )
    (net (code "62") (name "unconnected-(R4-Pad4)") (class "Default")
      (node (ref "R4") (pin "4") (pinfunction "4_4") (pintype "passive+no_connect"))
    )
    (net (code "63") (name "unconnected-(R4-Pad5)") (class "Default")
      (node (ref "R4") (pin "5") (pinfunction "5_5") (pintype "passive+no_connect"))
    )
    (net (code "64") (name "unconnected-(USB1-D+-Pad3)") (class "Default")
      (node (ref "USB1") (pin "3") (pinfunction "D+_3") (pintype "passive+no_connect"))
    )
    (net (code "65") (name "unconnected-(USB1-D--Pad2)") (class "Default")
      (node (ref "USB1") (pin "2") (pinfunction "D-_2") (pintype "passive+no_connect"))
    )
    (net (code "66") (name "unconnected-(USB1-ID-Pad4)") (class "Default")
      (node (ref "USB1") (pin "4") (pinfunction "ID_4") (pintype "passive+no_connect"))
    )
    (net (code "67") (name "unconnected-(X1-NC-Pad1)") (class "Default")
      (node (ref "X1") (pin "1") (pinfunction "NC_1") (pintype "passive+no_connect"))
    )
  )
)
